# 03-5V_To_3V3.net
KiCad netlist of a schematic drawn in Altium Designer
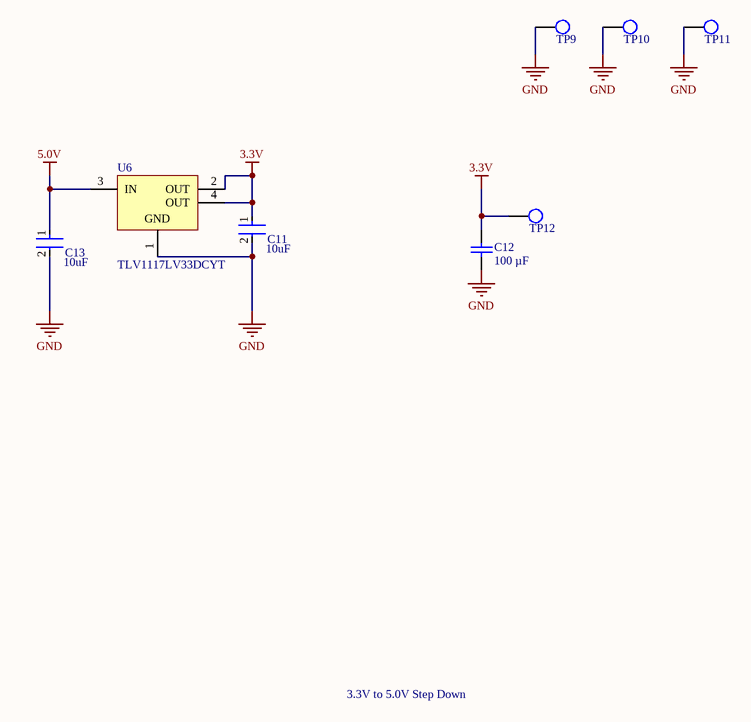
[diagram p0: 03-5V_To_3V3.SchDoc]

(export (version "E")
  (design (tool "Eeschema 10.0.6"))
  (components
    (comp (ref "C11")
      (value "CL21A106KQCLNNC")
      (footprint "FP-CL21-IPC_B")
      (description "CL21 Series 0805 10uF 6.3V ±10% Tolerance X5R Multilayer Ceramic Chip Capacitor")
      (fields (field (name "CAPACITANCE") "10uF") (field (name "TOLERANCE") "10%"))
      (libsource (lib "Altium Content Vault") (part "b4654b650e69147ec39a6b967a45e02"))
    )
    (comp (ref "C12")
      (value "EEEHA1A101WP")
      (footprint "CAP_EEEHA1A101WP")
      (description "100ÂµF 10V Aluminum Electrolytic Capacitors Radial, Can - SMD 1000 Hrs @ 105Â°C")
      (fields
        (field (name "MF") "Panasonic")
        (field (name "MP") "EEE-HA1A101WP")
        (field (name "CAPACITANCE") "100 µF")
      )
      (libsource (lib "team6") (part "EEEHA1A101WP"))
    )
    (comp (ref "C13")
      (value "CL21A106KQCLNNC")
      (footprint "FP-CL21-IPC_B")
      (description "CL21 Series 0805 10uF 6.3V ±10% Tolerance X5R Multilayer Ceramic Chip Capacitor")
      (fields (field (name "CAPACITANCE") "10uF") (field (name "TOLERANCE") "10%"))
      (libsource (lib "Altium Content Vault") (part "b4654b650e69147ec39a6b967a45e02"))
    )
    (comp (ref "TP9")
      (value "TP_1206")
      (footprint "TP-SMC-1206")
      (description "Test Point SMD 1206")
      (fields
        (field (name "MANUFACTURER") "TE Connectivity (Tyco Electronics)")
        (field (name "MANUFACTURER PART NUMBER") "1625854-1")
      )
      (libsource (lib "ECE453-F22-Power") (part "TP_1206"))
    )
    (comp (ref "TP10")
      (value "TP_1206")
      (footprint "TP-SMC-1206")
      (description "Test Point SMD 1206")
      (fields
        (field (name "MANUFACTURER") "TE Connectivity (Tyco Electronics)")
        (field (name "MANUFACTURER PART NUMBER") "1625854-1")
      )
      (libsource (lib "ECE453-F22-Power") (part "TP_1206"))
    )
    (comp (ref "TP11")
      (value "TP_1206")
      (footprint "TP-SMC-1206")
      (description "Test Point SMD 1206")
      (fields
        (field (name "MANUFACTURER") "TE Connectivity (Tyco Electronics)")
        (field (name "MANUFACTURER PART NUMBER") "1625854-1")
      )
      (libsource (lib "ECE453-F22-Power") (part "TP_1206"))
    )
    (comp (ref "TP12")
      (value "TP_1206")
      (footprint "TP-SMC-1206")
      (description "Test Point SMD 1206")
      (fields
        (field (name "MANUFACTURER") "TE Connectivity (Tyco Electronics)")
        (field (name "MANUFACTURER PART NUMBER") "1625854-1")
      )
      (libsource (lib "ECE453-F22-Power") (part "TP_1206"))
    )
    (comp (ref "U6")
      (value "TLV1117LV33DCYT")
      (footprint "DCY0004A_M")
      (fields (field (name "MANUFACTURER") "Texas Instruments"))
      (libsource (lib "Altium Content Vault") (part "TI-TLV1117LV33DCY4"))
    )
  )
  (nets
    (net (code "1") (name "3.3V") (class "Default")
      (node (ref "C11") (pin "1") (pinfunction "1_1") (pintype "passive"))
      (node (ref "C12") (pin "2") (pinfunction "2_2") (pintype "passive"))
      (node (ref "TP12") (pin "1") (pintype "passive"))
      (node (ref "U6") (pin "2") (pinfunction "OUT_2") (pintype "power_in"))
      (node (ref "U6") (pin "4") (pinfunction "OUT_4") (pintype "power_in"))
    )
    (net (code "2") (name "5.0V") (class "Default")
      (node (ref "C13") (pin "1") (pinfunction "1_1") (pintype "passive"))
      (node (ref "U6") (pin "3") (pinfunction "IN_3") (pintype "power_in"))
    )
    (net (code "3") (name "GND") (class "Default")
      (node (ref "C11") (pin "2") (pinfunction "2_2") (pintype "passive"))
      (node (ref "C12") (pin "1") (pinfunction "1_1") (pintype "passive"))
      (node (ref "C13") (pin "2") (pinfunction "2_2") (pintype "passive"))
      (node (ref "TP10") (pin "1") (pintype "passive"))
      (node (ref "TP11") (pin "1") (pintype "passive"))
      (node (ref "TP9") (pin "1") (pintype "passive"))
      (node (ref "U6") (pin "1") (pinfunction "GND_1") (pintype "power_in"))
    )
  )
)
